# ProiectTSC_v38.net
KiCad netlist of a schematic drawn in EAGLE
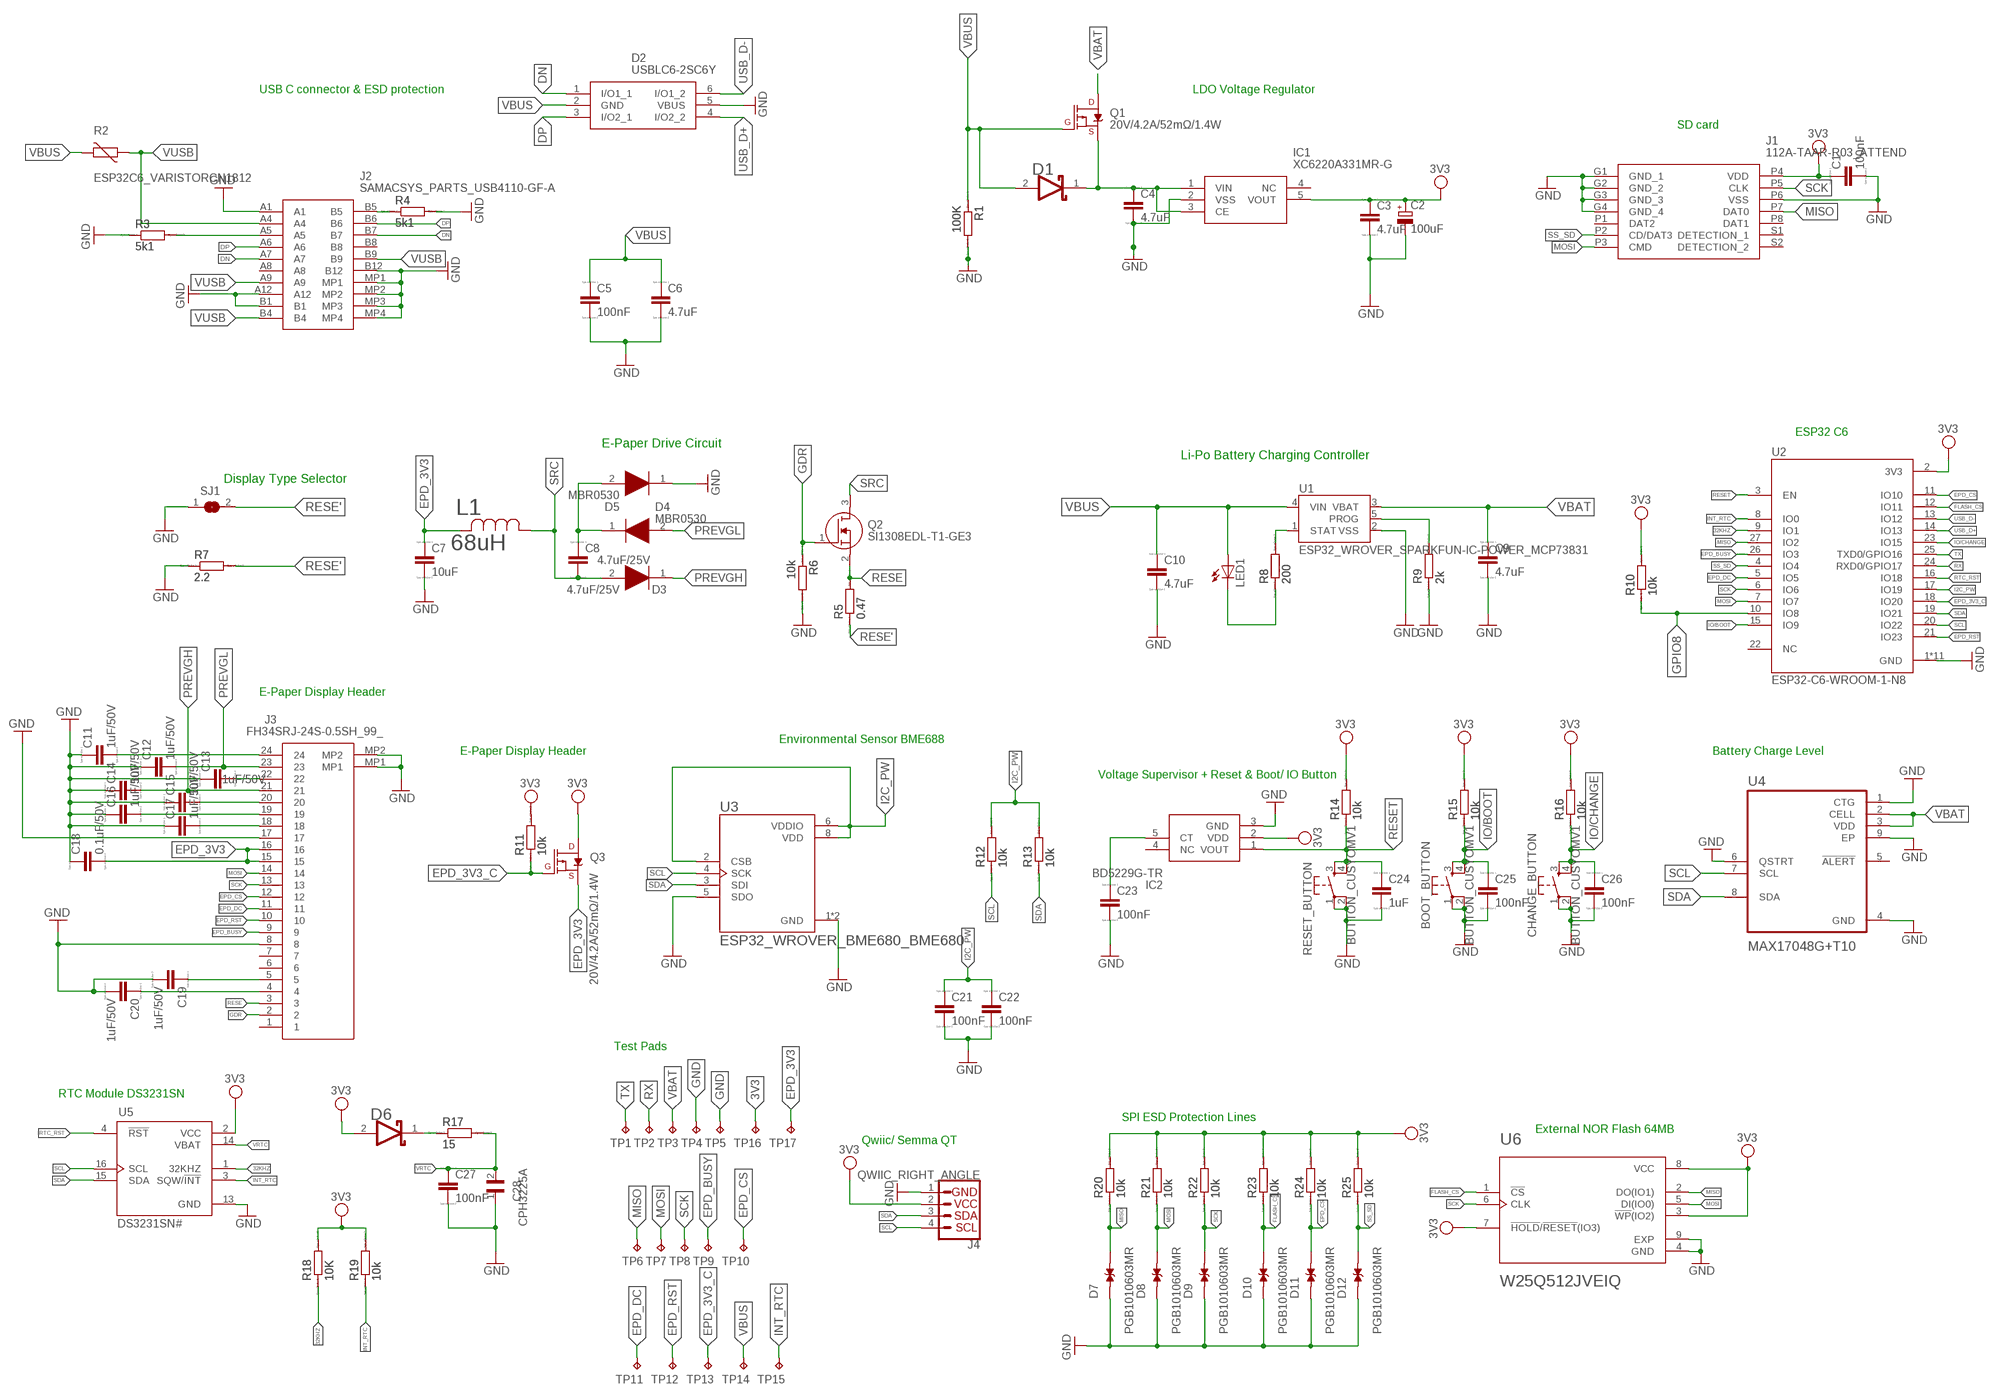
[diagram p0: schematic, sheet 1]

(export (version "E")
  (design (tool "Eeschema 10.0.6"))
  (components
    (comp (ref "BOOT_BUTTON")
      (value "BUTTON_CUSYOMV1")
      (footprint "eagle-import:MYBUTTON")
      (libsource (lib "eagle-import") (part "BUTTON_CUSYOMV1"))
    )
    (comp (ref "C1")
      (value "100nF")
      (footprint "eagle-import:EAGLE-LTSPICE_C0402")
      (libsource (lib "eagle-import") (part "EAGLE-LTSPICE_CC0402"))
    )
    (comp (ref "C2")
      (value "100uF")
      (footprint "eagle-import:RCL_CT3528")
      (libsource (lib "eagle-import") (part "RCL_CPOL-EUCT3528"))
    )
    (comp (ref "C3")
      (value "4.7uF")
      (footprint "eagle-import:ESP32_WROVER_EAGLE-LTSPICE_C0402")
      (libsource (lib "eagle-import") (part "ESP32_WROVER_EAGLE-LTSPICE_C"))
    )
    (comp (ref "C4")
      (value "4.7uF")
      (footprint "eagle-import:ESP32_WROVER_EAGLE-LTSPICE_C0402")
      (libsource (lib "eagle-import") (part "ESP32_WROVER_EAGLE-LTSPICE_C"))
    )
    (comp (ref "C5")
      (value "100nF")
      (footprint "eagle-import:EAGLE-LTSPICE_C0402")
      (libsource (lib "eagle-import") (part "EAGLE-LTSPICE_CC0402"))
    )
    (comp (ref "C6")
      (value "4.7uF")
      (footprint "eagle-import:EAGLE-LTSPICE_C0402")
      (libsource (lib "eagle-import") (part "EAGLE-LTSPICE_CC0402"))
    )
    (comp (ref "C7")
      (value "10uF")
      (footprint "eagle-import:EAGLE-LTSPICE_C0402")
      (libsource (lib "eagle-import") (part "EAGLE-LTSPICE_CC0402"))
    )
    (comp (ref "C8")
      (value "4.7uF/25V")
      (footprint "eagle-import:EAGLE-LTSPICE_C0402")
      (libsource (lib "eagle-import") (part "EAGLE-LTSPICE_CC0402"))
    )
    (comp (ref "C9")
      (value "4.7uF")
      (footprint "eagle-import:EAGLE-LTSPICE_C0402")
      (libsource (lib "eagle-import") (part "EAGLE-LTSPICE_CC0402"))
    )
    (comp (ref "C10")
      (value "4.7uF")
      (footprint "eagle-import:EAGLE-LTSPICE_C0402")
      (libsource (lib "eagle-import") (part "EAGLE-LTSPICE_CC0402"))
    )
    (comp (ref "C11")
      (value "1uF/50V")
      (footprint "eagle-import:EAGLE-LTSPICE_C0402")
      (libsource (lib "eagle-import") (part "EAGLE-LTSPICE_CC0402"))
    )
    (comp (ref "C12")
      (value "1uF/50V")
      (footprint "eagle-import:EAGLE-LTSPICE_C0402")
      (libsource (lib "eagle-import") (part "EAGLE-LTSPICE_CC0402"))
    )
    (comp (ref "C13")
      (value "1uF/50V")
      (footprint "eagle-import:EAGLE-LTSPICE_C0402")
      (libsource (lib "eagle-import") (part "EAGLE-LTSPICE_CC0402"))
    )
    (comp (ref "C14")
      (value "1uF/50V")
      (footprint "eagle-import:EAGLE-LTSPICE_C0402")
      (libsource (lib "eagle-import") (part "EAGLE-LTSPICE_CC0402"))
    )
    (comp (ref "C15")
      (value "1uF/50V")
      (footprint "eagle-import:EAGLE-LTSPICE_C0402")
      (libsource (lib "eagle-import") (part "EAGLE-LTSPICE_CC0402"))
    )
    (comp (ref "C16")
      (value "1uF/50V")
      (footprint "eagle-import:EAGLE-LTSPICE_C0402")
      (libsource (lib "eagle-import") (part "EAGLE-LTSPICE_CC0402"))
    )
    (comp (ref "C17")
      (value "1uF/50V")
      (footprint "eagle-import:EAGLE-LTSPICE_C0402")
      (libsource (lib "eagle-import") (part "EAGLE-LTSPICE_CC0402"))
    )
    (comp (ref "C18")
      (value "0.1uF/50V")
      (footprint "eagle-import:EAGLE-LTSPICE_C0402")
      (libsource (lib "eagle-import") (part "EAGLE-LTSPICE_CC0402"))
    )
    (comp (ref "C19")
      (value "1uF/50V")
      (footprint "eagle-import:EAGLE-LTSPICE_C0402")
      (libsource (lib "eagle-import") (part "EAGLE-LTSPICE_CC0402"))
    )
    (comp (ref "C20")
      (value "1uF/50V")
      (footprint "eagle-import:EAGLE-LTSPICE_C0402")
      (libsource (lib "eagle-import") (part "EAGLE-LTSPICE_CC0402"))
    )
    (comp (ref "C21")
      (value "100nF")
      (footprint "eagle-import:EAGLE-LTSPICE_C0402")
      (libsource (lib "eagle-import") (part "EAGLE-LTSPICE_CC0402"))
    )
    (comp (ref "C22")
      (value "100nF")
      (footprint "eagle-import:EAGLE-LTSPICE_C0402")
      (libsource (lib "eagle-import") (part "EAGLE-LTSPICE_CC0402"))
    )
    (comp (ref "C23")
      (value "100nF")
      (footprint "eagle-import:EAGLE-LTSPICE_C0402")
      (libsource (lib "eagle-import") (part "EAGLE-LTSPICE_CC0402"))
    )
    (comp (ref "C24")
      (value "1uF")
      (footprint "eagle-import:EAGLE-LTSPICE_C0402")
      (libsource (lib "eagle-import") (part "EAGLE-LTSPICE_CC0402"))
    )
    (comp (ref "C25")
      (value "100nF")
      (footprint "eagle-import:EAGLE-LTSPICE_C0402")
      (libsource (lib "eagle-import") (part "EAGLE-LTSPICE_CC0402"))
    )
    (comp (ref "C26")
      (value "100nF")
      (footprint "eagle-import:EAGLE-LTSPICE_C0402")
      (libsource (lib "eagle-import") (part "EAGLE-LTSPICE_CC0402"))
    )
    (comp (ref "C27")
      (value "100nF")
      (footprint "eagle-import:EAGLE-LTSPICE_C0402")
      (libsource (lib "eagle-import") (part "EAGLE-LTSPICE_CC0402"))
    )
    (comp (ref "C28")
      (value "CPH3225A")
      (footprint "eagle-import:CAPCP3225X100N")
      (fields (field (name "MF") "Seiko Instruments"))
      (libsource (lib "eagle-import") (part "CPH3225A"))
    )
    (comp (ref "CHANGE_BUTTON")
      (value "BUTTON_CUSYOMV1")
      (footprint "eagle-import:MYBUTTON")
      (libsource (lib "eagle-import") (part "BUTTON_CUSYOMV1"))
    )
    (comp (ref "D1")
      (value "ESP32_WROVER_AVX---SD0805S020S1R0_AVX_SD0805S020S1R0_0_0AVX_SD0805S020S1R0_0_0")
      (footprint "eagle-import:ESP32_WROVER_AVX---SD0805S020S1R0_AVX_SD0805S020S1R0_0")
      (fields
        (field (name "DIGIKEY_PART_NUMBER") "478-7800-1-ND")
        (field (name "MF") "AVX")
        (field (name "MOUSER_PART_NUMBER") "581-SD0805S020S1R0")
      )
      (libsource (lib "eagle-import") (part "ESP32_WROVER_AVX---SD0805S020S1R0_AVX_SD0805S020S1R0_0_0AVX_SD0805S020S1R0_0_0"))
    )
    (comp (ref "D2")
      (value "USBLC6-2SC6Y")
      (footprint "eagle-import:SOT95P280X145-6N")
      (fields (field (name "MF") "STMicroelectronics"))
      (libsource (lib "eagle-import") (part "USBLC6-2SC6Y"))
    )
    (comp (ref "D3")
      (value "4.7uF/25V")
      (footprint "eagle-import:SOD3716X135N")
      (fields (field (name "MF") "ON Semiconductor") (field (name "MP") "MBR0530"))
      (libsource (lib "eagle-import") (part "MBR0530"))
    )
    (comp (ref "D4")
      (value "MBR0530")
      (footprint "eagle-import:SOD3716X135N")
      (fields (field (name "MF") "ON Semiconductor"))
      (libsource (lib "eagle-import") (part "MBR0530"))
    )
    (comp (ref "D5")
      (value "MBR0530")
      (footprint "eagle-import:SOD3716X135N")
      (fields (field (name "MF") "ON Semiconductor"))
      (libsource (lib "eagle-import") (part "MBR0530"))
    )
    (comp (ref "D6")
      (value "ESP32_WROVER_AVX---SD0805S020S1R0_AVX_SD0805S020S1R0_0_0AVX_SD0805S020S1R0_0_0")
      (footprint "eagle-import:ESP32_WROVER_AVX---SD0805S020S1R0_AVX_SD0805S020S1R0_0")
      (fields
        (field (name "DIGIKEY_PART_NUMBER") "478-7800-1-ND")
        (field (name "MF") "AVX")
        (field (name "MOUSER_PART_NUMBER") "581-SD0805S020S1R0")
      )
      (libsource (lib "eagle-import") (part "ESP32_WROVER_AVX---SD0805S020S1R0_AVX_SD0805S020S1R0_0_0AVX_SD0805S020S1R0_0_0"))
    )
    (comp (ref "D7")
      (value "PGB1010603MR")
      (footprint "eagle-import:DIOC1608X36N")
      (fields (field (name "MF") "Littelfuse Inc."))
      (libsource (lib "eagle-import") (part "PGB1010603MR"))
    )
    (comp (ref "D8")
      (value "PGB1010603MR")
      (footprint "eagle-import:DIOC1608X36N")
      (fields (field (name "MF") "Littelfuse Inc."))
      (libsource (lib "eagle-import") (part "PGB1010603MR"))
    )
    (comp (ref "D9")
      (value "PGB1010603MR")
      (footprint "eagle-import:DIOC1608X36N")
      (fields (field (name "MF") "Littelfuse Inc."))
      (libsource (lib "eagle-import") (part "PGB1010603MR"))
    )
    (comp (ref "D10")
      (value "PGB1010603MR")
      (footprint "eagle-import:DIOC1608X36N")
      (fields (field (name "MF") "Littelfuse Inc."))
      (libsource (lib "eagle-import") (part "PGB1010603MR"))
    )
    (comp (ref "D11")
      (value "PGB1010603MR")
      (footprint "eagle-import:DIOC1608X36N")
      (fields (field (name "MF") "Littelfuse Inc."))
      (libsource (lib "eagle-import") (part "PGB1010603MR"))
    )
    (comp (ref "D12")
      (value "PGB1010603MR")
      (footprint "eagle-import:DIOC1608X36N")
      (fields (field (name "MF") "Littelfuse Inc."))
      (libsource (lib "eagle-import") (part "PGB1010603MR"))
    )
    (comp (ref "IC1")
      (value "XC6220A331MR-G")
      (footprint "eagle-import:SOT95P280X120-5N")
      (fields (field (name "MOUSER_PART_NUMBER") "865-XC6220A331MR-G"))
      (libsource (lib "eagle-import") (part "XC6220A331MR-G"))
    )
    (comp (ref "IC2")
      (value "BD5229G-TR")
      (footprint "eagle-import:SOT95P280X125-5N")
      (fields (field (name "MOUSER_PART_NUMBER") "755-BD5229G-TR"))
      (libsource (lib "eagle-import") (part "BD5229G-TR"))
    )
    (comp (ref "J1")
      (value "112A-TAAR-R03_ATTEND")
      (footprint "eagle-import:112ATAARR03ATTEND")
      (fields (field (name "MANUFACTURER_PART_NUMBER") "112A-TAAR-R03 ATTEND"))
      (libsource (lib "eagle-import") (part "112A-TAAR-R03_ATTEND"))
    )
    (comp (ref "J2")
      (value "SAMACSYS_PARTS_USB4110-GF-A")
      (footprint "eagle-import:SAMACSYS_PARTS_USB4110GFA")
      (fields
        (field (name "MANUFACTURER_PART_NUMBER") "USB4110-GF-A")
        (field (name "MOUSER_PART_NUMBER") "640-USB4110-GF-A")
      )
      (libsource (lib "eagle-import") (part "SAMACSYS_PARTS_USB4110-GF-A"))
    )
    (comp (ref "J3")
      (value "FH34SRJ-24S-0.5SH_99_")
      (footprint "eagle-import:FH34SRJ24S05SH99")
      (fields
        (field (name "MANUFACTURER_PART_NUMBER") "FH34SRJ-24S-0.5SH(99)")
        (field (name "MOUSER_PART_NUMBER") "798-FH34SRJ24S05SH99")
      )
      (libsource (lib "eagle-import") (part "FH34SRJ-24S-0.5SH_99_"))
    )
    (comp (ref "J4")
      (value "QWIIC_RIGHT_ANGLE")
      (footprint "eagle-import:JST04_1MM_RA")
      (libsource (lib "eagle-import") (part "QWIIC_CONNECTORJS-1MM"))
    )
    (comp (ref "L1")
      (value "68uH")
      (footprint "eagle-import:IND_4828-WE-TPC_WRE")
      (fields
        (field (name "MANUFACTURER_PART_NUMBER") "744043680")
        (field (name "COPYRIGHT") "Copyright (C) 2024 Ultra Librarian. All rights reserved.")
      )
      (libsource (lib "eagle-import") (part "744043680IND_4828-WE-TPC_WRE"))
    )
    (comp (ref "LED1")
      (value "ADAFRUIT_LEDCHIP-LED0603")
      (footprint "eagle-import:ADAFRUIT_CHIP-LED0603")
      (libsource (lib "eagle-import") (part "ADAFRUIT_LEDCHIP-LED0603"))
    )
    (comp (ref "Q1")
      (value "20V/4.2A/52mΩ/1.4W")
      (footprint "eagle-import:ESP32_WROVER_SPARKFUN-DISCRETESEMI_SOT23-3")
      (libsource (lib "eagle-import") (part "ESP32_WROVER_SPARKFUN-DISCRETESEMI_MOSFET_PCH-DMG2305UX-7"))
    )
    (comp (ref "Q2")
      (value "SI1308EDL-T1-GE3")
      (footprint "eagle-import:SOT65P210X110-3N")
      (fields (field (name "MF") "Vishay Siliconix"))
      (libsource (lib "eagle-import") (part "SI1308EDL-T1-GE3"))
    )
    (comp (ref "Q3")
      (value "20V/4.2A/52mΩ/1.4W")
      (footprint "eagle-import:ESP32_WROVER_SPARKFUN-DISCRETESEMI_SOT23-3")
      (libsource (lib "eagle-import") (part "ESP32_WROVER_SPARKFUN-DISCRETESEMI_MOSFET_PCH-DMG2305UX-7"))
    )
    (comp (ref "R1")
      (value "100K")
      (footprint "eagle-import:ESP32_WROVER_EAGLE-LTSPICE_R0402")
      (libsource (lib "eagle-import") (part "ESP32_WROVER_EAGLE-LTSPICE_RR0402"))
    )
    (comp (ref "R2")
      (value "ESP32C6_VARISTORCN1812")
      (footprint "eagle-import:ESP32C6_VARISTOR_CT_CN1812")
      (libsource (lib "eagle-import") (part "ESP32C6_VARISTORCN1812"))
    )
    (comp (ref "R3")
      (value "5k1")
      (footprint "eagle-import:ESP32_WROVER_EAGLE-LTSPICE_R0402")
      (libsource (lib "eagle-import") (part "ESP32_WROVER_EAGLE-LTSPICE_RR0402"))
    )
    (comp (ref "R4")
      (value "5k1")
      (footprint "eagle-import:ESP32_WROVER_EAGLE-LTSPICE_R0402")
      (libsource (lib "eagle-import") (part "ESP32_WROVER_EAGLE-LTSPICE_RR0402"))
    )
    (comp (ref "R5")
      (value "0.47")
      (footprint "eagle-import:ESP32_WROVER_EAGLE-LTSPICE_R0402")
      (libsource (lib "eagle-import") (part "ESP32_WROVER_EAGLE-LTSPICE_RR0402"))
    )
    (comp (ref "R6")
      (value "10k")
      (footprint "eagle-import:ESP32_WROVER_EAGLE-LTSPICE_R0402")
      (libsource (lib "eagle-import") (part "ESP32_WROVER_EAGLE-LTSPICE_RR0402"))
    )
    (comp (ref "R7")
      (value "2.2")
      (footprint "eagle-import:ESP32_WROVER_EAGLE-LTSPICE_R0402")
      (libsource (lib "eagle-import") (part "ESP32_WROVER_EAGLE-LTSPICE_RR0402"))
    )
    (comp (ref "R8")
      (value "200")
      (footprint "eagle-import:ESP32_WROVER_EAGLE-LTSPICE_R0402")
      (libsource (lib "eagle-import") (part "ESP32_WROVER_EAGLE-LTSPICE_RR0402"))
    )
    (comp (ref "R9")
      (value "2k")
      (footprint "eagle-import:ESP32_WROVER_EAGLE-LTSPICE_R0402")
      (libsource (lib "eagle-import") (part "ESP32_WROVER_EAGLE-LTSPICE_RR0402"))
    )
    (comp (ref "R10")
      (value "10k")
      (footprint "eagle-import:ESP32_WROVER_EAGLE-LTSPICE_R0402")
      (libsource (lib "eagle-import") (part "ESP32_WROVER_EAGLE-LTSPICE_RR0402"))
    )
    (comp (ref "R11")
      (value "10k")
      (footprint "eagle-import:ESP32_WROVER_EAGLE-LTSPICE_R0402")
      (libsource (lib "eagle-import") (part "ESP32_WROVER_EAGLE-LTSPICE_RR0402"))
    )
    (comp (ref "R12")
      (value "10k")
      (footprint "eagle-import:ESP32_WROVER_EAGLE-LTSPICE_R0402")
      (libsource (lib "eagle-import") (part "ESP32_WROVER_EAGLE-LTSPICE_RR0402"))
    )
    (comp (ref "R13")
      (value "10k")
      (footprint "eagle-import:ESP32_WROVER_EAGLE-LTSPICE_R0402")
      (libsource (lib "eagle-import") (part "ESP32_WROVER_EAGLE-LTSPICE_RR0402"))
    )
    (comp (ref "R14")
      (value "10k")
      (footprint "eagle-import:ESP32_WROVER_EAGLE-LTSPICE_R0402")
      (libsource (lib "eagle-import") (part "ESP32_WROVER_EAGLE-LTSPICE_RR0402"))
    )
    (comp (ref "R15")
      (value "10k")
      (footprint "eagle-import:ESP32_WROVER_EAGLE-LTSPICE_R0402")
      (libsource (lib "eagle-import") (part "ESP32_WROVER_EAGLE-LTSPICE_RR0402"))
    )
    (comp (ref "R16")
      (value "10k")
      (footprint "eagle-import:ESP32_WROVER_EAGLE-LTSPICE_R0402")
      (libsource (lib "eagle-import") (part "ESP32_WROVER_EAGLE-LTSPICE_RR0402"))
    )
    (comp (ref "R17")
      (value "15")
      (footprint "eagle-import:ESP32_WROVER_EAGLE-LTSPICE_R0402")
      (libsource (lib "eagle-import") (part "ESP32_WROVER_EAGLE-LTSPICE_RR0402"))
    )
    (comp (ref "R18")
      (value "10K")
      (footprint "eagle-import:ESP32_WROVER_EAGLE-LTSPICE_R0402")
      (libsource (lib "eagle-import") (part "ESP32_WROVER_EAGLE-LTSPICE_RR0402"))
    )
    (comp (ref "R19")
      (value "10k")
      (footprint "eagle-import:ESP32_WROVER_EAGLE-LTSPICE_R0402")
      (libsource (lib "eagle-import") (part "ESP32_WROVER_EAGLE-LTSPICE_RR0402"))
    )
    (comp (ref "R20")
      (value "10k")
      (footprint "eagle-import:ESP32_WROVER_EAGLE-LTSPICE_R0402")
      (libsource (lib "eagle-import") (part "ESP32_WROVER_EAGLE-LTSPICE_RR0402"))
    )
    (comp (ref "R21")
      (value "10k")
      (footprint "eagle-import:ESP32_WROVER_EAGLE-LTSPICE_R0402")
      (libsource (lib "eagle-import") (part "ESP32_WROVER_EAGLE-LTSPICE_RR0402"))
    )
    (comp (ref "R22")
      (value "10k")
      (footprint "eagle-import:ESP32_WROVER_EAGLE-LTSPICE_R0402")
      (libsource (lib "eagle-import") (part "ESP32_WROVER_EAGLE-LTSPICE_RR0402"))
    )
    (comp (ref "R23")
      (value "10k")
      (footprint "eagle-import:ESP32_WROVER_EAGLE-LTSPICE_R0402")
      (libsource (lib "eagle-import") (part "ESP32_WROVER_EAGLE-LTSPICE_RR0402"))
    )
    (comp (ref "R24")
      (value "10k")
      (footprint "eagle-import:ESP32_WROVER_EAGLE-LTSPICE_R0402")
      (libsource (lib "eagle-import") (part "ESP32_WROVER_EAGLE-LTSPICE_RR0402"))
    )
    (comp (ref "R25")
      (value "10k")
      (footprint "eagle-import:ESP32_WROVER_EAGLE-LTSPICE_R0402")
      (libsource (lib "eagle-import") (part "ESP32_WROVER_EAGLE-LTSPICE_RR0402"))
    )
    (comp (ref "RESET_BUTTON")
      (value "BUTTON_CUSYOMV1")
      (footprint "eagle-import:MYBUTTON")
      (libsource (lib "eagle-import") (part "BUTTON_CUSYOMV1"))
    )
    (comp (ref "SJ1") (value "SJ") (footprint "eagle-import:SJ") (libsource (lib "eagle-import") (part "SJ")))
    (comp (ref "TP1")
      (value "TPTP20R")
      (footprint "eagle-import:TP20R")
      (libsource (lib "eagle-import") (part "TPTP20R"))
    )
    (comp (ref "TP2")
      (value "TPTP20R")
      (footprint "eagle-import:TP20R")
      (libsource (lib "eagle-import") (part "TPTP20R"))
    )
    (comp (ref "TP3")
      (value "TPTP20R")
      (footprint "eagle-import:TP20R")
      (libsource (lib "eagle-import") (part "TPTP20R"))
    )
    (comp (ref "TP4")
      (value "TPTP20R")
      (footprint "eagle-import:TP20R")
      (libsource (lib "eagle-import") (part "TPTP20R"))
    )
    (comp (ref "TP5")
      (value "TPTP20R")
      (footprint "eagle-import:TP20R")
      (libsource (lib "eagle-import") (part "TPTP20R"))
    )
    (comp (ref "TP6")
      (value "TPTP20R")
      (footprint "eagle-import:TP20R")
      (libsource (lib "eagle-import") (part "TPTP20R"))
    )
    (comp (ref "TP7")
      (value "TPTP20R")
      (footprint "eagle-import:TP20R")
      (libsource (lib "eagle-import") (part "TPTP20R"))
    )
    (comp (ref "TP8")
      (value "TPTP20R")
      (footprint "eagle-import:TP20R")
      (libsource (lib "eagle-import") (part "TPTP20R"))
    )
    (comp (ref "TP9")
      (value "TPTP20R")
      (footprint "eagle-import:TP20R")
      (libsource (lib "eagle-import") (part "TPTP20R"))
    )
    (comp (ref "TP10")
      (value "TPTP20R")
      (footprint "eagle-import:TP20R")
      (libsource (lib "eagle-import") (part "TPTP20R"))
    )
    (comp (ref "TP11")
      (value "TPTP20R")
      (footprint "eagle-import:TP20R")
      (libsource (lib "eagle-import") (part "TPTP20R"))
    )
    (comp (ref "TP12")
      (value "TPTP20R")
      (footprint "eagle-import:TP20R")
      (libsource (lib "eagle-import") (part "TPTP20R"))
    )
    (comp (ref "TP13")
      (value "TPTP20R")
      (footprint "eagle-import:TP20R")
      (libsource (lib "eagle-import") (part "TPTP20R"))
    )
    (comp (ref "TP14")
      (value "TPTP20R")
      (footprint "eagle-import:TP20R")
      (libsource (lib "eagle-import") (part "TPTP20R"))
    )
    (comp (ref "TP15")
      (value "TPTP20R")
      (footprint "eagle-import:TP20R")
      (libsource (lib "eagle-import") (part "TPTP20R"))
    )
    (comp (ref "TP16")
      (value "TPTP20R")
      (footprint "eagle-import:TP20R")
      (libsource (lib "eagle-import") (part "TPTP20R"))
    )
    (comp (ref "TP17")
      (value "TPTP20R")
      (footprint "eagle-import:TP20R")
      (libsource (lib "eagle-import") (part "TPTP20R"))
    )
    (comp (ref "U1")
      (value "ESP32_WROVER_SPARKFUN-IC-POWER_MCP73831")
      (footprint "eagle-import:ESP32_WROVER_SPARKFUN-IC-POWER_SOT23-5")
      (libsource (lib "eagle-import") (part "ESP32_WROVER_SPARKFUN-IC-POWER_MCP73831"))
    )
    (comp (ref "U2")
      (value "ESP32-C6-WROOM-1-N8")
      (footprint "eagle-import:XCVR_ESP32-C6-WROOM-1-N8")
      (fields (field (name "MF") "Espressif Systems"))
      (libsource (lib "eagle-import") (part "ESP32-C6-WROOM-1-N8"))
    )
    (comp (ref "U3")
      (value "ESP32_WROVER_BME680_BME680")
      (footprint "eagle-import:ESP32_WROVER_BME680_PSON80P300X300X100-8N")
      (fields (field (name "MF") "Bosch Sensortec") (field (name "MP") "BME680"))
      (libsource (lib "eagle-import") (part "ESP32_WROVER_BME680_BME680"))
    )
    (comp (ref "U4")
      (value "MAX17048G+T10")
      (footprint "eagle-import:SON50P200X200X80-9N")
      (fields (field (name "MF") "Analog Devices"))
      (libsource (lib "eagle-import") (part "MAX17048G+T10"))
    )
    (comp (ref "U5")
      (value "DS3231SN#")
      (footprint "eagle-import:SOIC127P1032X265-16N")
      (fields (field (name "MF") "Analog Devices"))
      (libsource (lib "eagle-import") (part "DS3231SN#"))
    )
    (comp (ref "U6")
      (value "W25Q512JVEIQ")
      (footprint "eagle-import:SON127P600X800X80-9N")
      (fields (field (name "MF") "Winbond Electronics"))
      (libsource (lib "eagle-import") (part "W25Q512JVEIQ"))
    )
  )
  (nets
    (net (code "1") (name "3V3") (class "Default")
      (node (ref "C1") (pin "1") (pinfunction "1_1") (pintype "passive"))
      (node (ref "C2") (pin "+") (pinfunction "+_+") (pintype "passive"))
      (node (ref "C3") (pin "1") (pinfunction "1_1") (pintype "passive"))
      (node (ref "D6") (pin "2") (pinfunction "ANODE_2") (pintype "bidirectional"))
      (node (ref "IC1") (pin "5") (pinfunction "VOUT_5") (pintype "bidirectional"))
      (node (ref "IC2") (pin "2") (pinfunction "VDD_2") (pintype "bidirectional"))
      (node (ref "J1") (pin "P4") (pinfunction "VDD_P4") (pintype "bidirectional"))
      (node (ref "J4") (pin "2") (pinfunction "2_2") (pintype "power_in"))
      (node (ref "Q3") (pin "3") (pinfunction "D_3") (pintype "bidirectional"))
      (node (ref "R10") (pin "2") (pinfunction "2_2") (pintype "passive"))
      (node (ref "R11") (pin "2") (pinfunction "2_2") (pintype "passive"))
      (node (ref "R14") (pin "2") (pinfunction "2_2") (pintype "passive"))
      (node (ref "R15") (pin "2") (pinfunction "2_2") (pintype "passive"))
      (node (ref "R16") (pin "2") (pinfunction "2_2") (pintype "passive"))
      (node (ref "R18") (pin "2") (pinfunction "2_2") (pintype "passive"))
      (node (ref "R19") (pin "2") (pinfunction "2_2") (pintype "passive"))
      (node (ref "R20") (pin "2") (pinfunction "2_2") (pintype "passive"))
      (node (ref "R21") (pin "2") (pinfunction "2_2") (pintype "passive"))
      (node (ref "R22") (pin "2") (pinfunction "2_2") (pintype "passive"))
      (node (ref "R23") (pin "2") (pinfunction "2_2") (pintype "passive"))
      (node (ref "R24") (pin "2") (pinfunction "2_2") (pintype "passive"))
      (node (ref "R25") (pin "2") (pinfunction "2_2") (pintype "passive"))
      (node (ref "TP16") (pin "TP") (pinfunction "TP_TP") (pintype "input"))
      (node (ref "U2") (pin "2") (pinfunction "3V3_2") (pintype "power_in"))
      (node (ref "U5") (pin "2") (pinfunction "VCC_2") (pintype "power_in"))
      (node (ref "U6") (pin "3") (pinfunction "~{WP}(IO2)_3") (pintype "bidirectional"))
      (node (ref "U6") (pin "7") (pinfunction "~{HOLD}/~{RESET}(IO3)_7") (pintype "bidirectional"))
      (node (ref "U6") (pin "8") (pinfunction "VCC_8") (pintype "power_in"))
    )
    (net (code "2") (name "32KHZ") (class "Default")
      (node (ref "R18") (pin "1") (pinfunction "1_1") (pintype "passive"))
      (node (ref "U2") (pin "9") (pinfunction "IO1_9") (pintype "bidirectional"))
      (node (ref "U5") (pin "1") (pinfunction "32KHZ_1") (pintype "output"))
    )
    (net (code "3") (name "DN") (class "Default")
      (node (ref "D2") (pin "1") (pinfunction "I/O1_1_1") (pintype "bidirectional"))
      (node (ref "J2") (pin "A7") (pinfunction "A7_A7") (pintype "bidirectional"))
      (node (ref "J2") (pin "B7") (pinfunction "B7_B7") (pintype "bidirectional"))
    )
    (net (code "4") (name "DP") (class "Default")
      (node (ref "D2") (pin "3") (pinfunction "I/O2_1_3") (pintype "bidirectional"))
      (node (ref "J2") (pin "A6") (pinfunction "A6_A6") (pintype "bidirectional"))
      (node (ref "J2") (pin "B6") (pinfunction "B6_B6") (pintype "bidirectional"))
    )
    (net (code "5") (name "EPD_3V3") (class "Default")
      (node (ref "C18") (pin "2") (pinfunction "2_2") (pintype "passive"))
      (node (ref "C7") (pin "1") (pinfunction "1_1") (pintype "passive"))
      (node (ref "J3") (pin "15") (pinfunction "15_15") (pintype "bidirectional"))
      (node (ref "J3") (pin "16") (pinfunction "16_16") (pintype "bidirectional"))
      (node (ref "L1") (pin "2") (pinfunction "2_2") (pintype "passive"))
      (node (ref "Q3") (pin "2") (pinfunction "S_2") (pintype "bidirectional"))
      (node (ref "TP17") (pin "TP") (pinfunction "TP_TP") (pintype "input"))
    )
    (net (code "6") (name "EPD_3V3_C") (class "Default")
      (node (ref "Q3") (pin "1") (pinfunction "G_1") (pintype "bidirectional"))
      (node (ref "R11") (pin "1") (pinfunction "1_1") (pintype "passive"))
      (node (ref "TP13") (pin "TP") (pinfunction "TP_TP") (pintype "input"))
      (node (ref "U2") (pin "18") (pinfunction "IO20_18") (pintype "bidirectional"))
    )
    (net (code "7") (name "EPD_BUSY") (class "Default")
      (node (ref "J3") (pin "9") (pinfunction "9_9") (pintype "bidirectional"))
      (node (ref "TP9") (pin "TP") (pinfunction "TP_TP") (pintype "input"))
      (node (ref "U2") (pin "26") (pinfunction "IO3_26") (pintype "bidirectional"))
    )
    (net (code "8") (name "EPD_CS") (class "Default")
      (node (ref "D11") (pin "2") (pinfunction "2_2") (pintype "passive"))
      (node (ref "J3") (pin "12") (pinfunction "12_12") (pintype "bidirectional"))
      (node (ref "R24") (pin "1") (pinfunction "1_1") (pintype "passive"))
      (node (ref "TP10") (pin "TP") (pinfunction "TP_TP") (pintype "input"))
      (node (ref "U2") (pin "11") (pinfunction "IO10_11") (pintype "bidirectional"))
    )
    (net (code "9") (name "EPD_DC") (class "Default")
      (node (ref "J3") (pin "11") (pinfunction "11_11") (pintype "bidirectional"))
      (node (ref "TP11") (pin "TP") (pinfunction "TP_TP") (pintype "input"))
      (node (ref "U2") (pin "5") (pinfunction "IO5_5") (pintype "bidirectional"))
    )
    (net (code "10") (name "EPD_RST") (class "Default")
      (node (ref "J3") (pin "10") (pinfunction "10_10") (pintype "bidirectional"))
      (node (ref "TP12") (pin "TP") (pinfunction "TP_TP") (pintype "input"))
      (node (ref "U2") (pin "21") (pinfunction "IO23_21") (pintype "bidirectional"))
    )
    (net (code "11") (name "FLASH_CS") (class "Default")
      (node (ref "D10") (pin "2") (pinfunction "2_2") (pintype "passive"))
      (node (ref "R23") (pin "1") (pinfunction "1_1") (pintype "passive"))
      (node (ref "U2") (pin "12") (pinfunction "IO11_12") (pintype "bidirectional"))
      (node (ref "U6") (pin "1") (pinfunction "~{CS}_1") (pintype "input"))
    )
    (net (code "12") (name "GDR") (class "Default")
      (node (ref "J3") (pin "2") (pinfunction "2_2") (pintype "bidirectional"))
      (node (ref "Q2") (pin "1") (pinfunction "G_1") (pintype "bidirectional"))
      (node (ref "R6") (pin "1") (pinfunction "1_1") (pintype "passive"))
    )
    (net (code "13") (name "GND") (class "Default")
      (node (ref "BOOT_BUTTON") (pin "1") (pinfunction "1_1") (pintype "passive"))
      (node (ref "BOOT_BUTTON") (pin "2") (pinfunction "2_2") (pintype "passive"))
      (node (ref "C1") (pin "2") (pinfunction "2_2") (pintype "passive"))
      (node (ref "C10") (pin "2") (pinfunction "2_2") (pintype "passive"))
      (node (ref "C11") (pin "1") (pinfunction "1_1") (pintype "passive"))
      (node (ref "C12") (pin "1") (pinfunction "1_1") (pintype "passive"))
      (node (ref "C13") (pin "1") (pinfunction "1_1") (pintype "passive"))
      (node (ref "C14") (pin "1") (pinfunction "1_1") (pintype "passive"))
      (node (ref "C15") (pin "1") (pinfunction "1_1") (pintype "passive"))
      (node (ref "C16") (pin "1") (pinfunction "1_1") (pintype "passive"))
      (node (ref "C17") (pin "1") (pinfunction "1_1") (pintype "passive"))
      (node (ref "C18") (pin "1") (pinfunction "1_1") (pintype "passive"))
      (node (ref "C19") (pin "2") (pinfunction "2_2") (pintype "passive"))
      (node (ref "C2") (pin "-") (pinfunction "-_-") (pintype "passive"))
      (node (ref "C20") (pin "2") (pinfunction "2_2") (pintype "passive"))
      (node (ref "C21") (pin "2") (pinfunction "2_2") (pintype "passive"))
      (node (ref "C22") (pin "2") (pinfunction "2_2") (pintype "passive"))
      (node (ref "C23") (pin "2") (pinfunction "2_2") (pintype "passive"))
      (node (ref "C24") (pin "2") (pinfunction "2_2") (pintype "passive"))
      (node (ref "C25") (pin "2") (pinfunction "2_2") (pintype "passive"))
      (node (ref "C26") (pin "2") (pinfunction "2_2") (pintype "passive"))
      (node (ref "C27") (pin "2") (pinfunction "2_2") (pintype "passive"))
      (node (ref "C28") (pin "1") (pinfunction "1_1") (pintype "passive"))
      (node (ref "C3") (pin "2") (pinfunction "2_2") (pintype "passive"))
      (node (ref "C4") (pin "2") (pinfunction "2_2") (pintype "passive"))
      (node (ref "C5") (pin "2") (pinfunction "2_2") (pintype "passive"))
      (node (ref "C6") (pin "2") (pinfunction "2_2") (pintype "passive"))
      (node (ref "C7") (pin "2") (pinfunction "2_2") (pintype "passive"))
      (node (ref "C9") (pin "2") (pinfunction "2_2") (pintype "passive"))
      (node (ref "CHANGE_BUTTON") (pin "1") (pinfunction "1_1") (pintype "passive"))
      (node (ref "CHANGE_BUTTON") (pin "2") (pinfunction "2_2") (pintype "passive"))
      (node (ref "D10") (pin "1") (pinfunction "1_1") (pintype "passive"))
      (node (ref "D11") (pin "1") (pinfunction "1_1") (pintype "passive"))
      (node (ref "D12") (pin "1") (pinfunction "1_1") (pintype "passive"))
      (node (ref "D2") (pin "5") (pinfunction "VBUS_5") (pintype "bidirectional"))
      (node (ref "D5") (pin "1") (pinfunction "K_1") (pintype "bidirectional"))
      (node (ref "D7") (pin "1") (pinfunction "1_1") (pintype "passive"))
      (node (ref "D8") (pin "1") (pinfunction "1_1") (pintype "passive"))
      (node (ref "D9") (pin "1") (pinfunction "1_1") (pintype "passive"))
      (node (ref "IC1") (pin "2") (pinfunction "VSS_2") (pintype "bidirectional"))
      (node (ref "IC2") (pin "3") (pinfunction "GND_3") (pintype "bidirectional"))
      (node (ref "J1") (pin "G1") (pinfunction "GND_1_G1") (pintype "bidirectional"))
      (node (ref "J1") (pin "G2") (pinfunction "GND_2_G2") (pintype "bidirectional"))
      (node (ref "J1") (pin "G3") (pinfunction "GND_3_G3") (pintype "bidirectional"))
      (node (ref "J1") (pin "G4") (pinfunction "GND_4_G4") (pintype "bidirectional"))
      (node (ref "J1") (pin "P6") (pinfunction "VSS_P6") (pintype "bidirectional"))
      (node (ref "J2") (pin "A1") (pinfunction "A1_A1") (pintype "bidirectional"))
      (node (ref "J2") (pin "A12") (pinfunction "A12_A12") (pintype "bidirectional"))
      (node (ref "J2") (pin "B1") (pinfunction "B1_B1") (pintype "bidirectional"))
      (node (ref "J2") (pin "B12") (pinfunction "B12_B12") (pintype "bidirectional"))
      (node (ref "J2") (pin "MP1") (pinfunction "MP1_MP1") (pintype "bidirectional"))
      (node (ref "J2") (pin "MP2") (pinfunction "MP2_MP2") (pintype "bidirectional"))
      (node (ref "J2") (pin "MP3") (pinfunction "MP3_MP3") (pintype "bidirectional"))
      (node (ref "J2") (pin "MP4") (pinfunction "MP4_MP4") (pintype "bidirectional"))
      (node (ref "J3") (pin "17") (pinfunction "17_17") (pintype "bidirectional"))
      (node (ref "J3") (pin "8") (pinfunction "8_8") (pintype "bidirectional"))
      (node (ref "J3") (pin "MP1") (pinfunction "MP1_MP1") (pintype "bidirectional"))
      (node (ref "J3") (pin "MP2") (pinfunction "MP2_MP2") (pintype "bidirectional"))
      (node (ref "J4") (pin "1") (pinfunction "1_1") (pintype "power_in"))
      (node (ref "R1") (pin "2") (pinfunction "2_2") (pintype "passive"))
      (node (ref "R3") (pin "1") (pinfunction "1_1") (pintype "passive"))
      (node (ref "R4") (pin "2") (pinfunction "2_2") (pintype "passive"))
      (node (ref "R6") (pin "2") (pinfunction "2_2") (pintype "passive"))
      (node (ref "R7") (pin "1") (pinfunction "1_1") (pintype "passive"))
      (node (ref "R9") (pin "1") (pinfunction "1_1") (pintype "passive"))
      (node (ref "RESET_BUTTON") (pin "1") (pinfunction "1_1") (pintype "passive"))
      (node (ref "RESET_BUTTON") (pin "2") (pinfunction "2_2") (pintype "passive"))
      (node (ref "SJ1") (pin "1") (pinfunction "1_1") (pintype "passive"))
      (node (ref "TP4") (pin "TP") (pinfunction "TP_TP") (pintype "input"))
      (node (ref "TP5") (pin "TP") (pinfunction "TP_TP") (pintype "input"))
      (node (ref "U1") (pin "2") (pinfunction "VSS_2") (pintype "power_in"))
      (node (ref "U2") (pin "1") (pinfunction "GND_1") (pintype "power_in"))
      (node (ref "U2") (pin "28") (pinfunction "GND_28") (pintype "power_in"))
      (node (ref "U2") (pin "29_1") (pinfunction "GND_29_1") (pintype "power_in"))
      (node (ref "U2") (pin "29_2") (pinfunction "GND_29_2") (pintype "power_in"))
      (node (ref "U2") (pin "29_3") (pinfunction "GND_29_3") (pintype "power_in"))
      (node (ref "U2") (pin "29_4") (pinfunction "GND_29_4") (pintype "power_in"))
      (node (ref "U2") (pin "29_5") (pinfunction "GND_29_5") (pintype "power_in"))
      (node (ref "U2") (pin "29_6") (pinfunction "GND_29_6") (pintype "power_in"))
      (node (ref "U2") (pin "29_7") (pinfunction "GND_29_7") (pintype "power_in"))
      (node (ref "U2") (pin "29_8") (pinfunction "GND_29_8") (pintype "power_in"))
      (node (ref "U2") (pin "29_9") (pinfunction "GND_29_9") (pintype "power_in"))
      (node (ref "U3") (pin "1") (pinfunction "GND_1") (pintype "power_in"))
      (node (ref "U3") (pin "5") (pinfunction "SDO_5") (pintype "bidirectional"))
      (node (ref "U3") (pin "7") (pinfunction "GND_7") (pintype "power_in"))
      (node (ref "U4") (pin "1") (pinfunction "CTG_1") (pintype "power_in"))
      (node (ref "U4") (pin "4") (pinfunction "GND_4") (pintype "power_in"))
      (node (ref "U4") (pin "6") (pinfunction "QSTRT_6") (pintype "input"))
      (node (ref "U4") (pin "9") (pinfunction "EP_9") (pintype "power_in"))
      (node (ref "U5") (pin "13") (pinfunction "GND_13") (pintype "power_in"))
      (node (ref "U6") (pin "4") (pinfunction "GND_4") (pintype "power_in"))
      (node (ref "U6") (pin "9") (pinfunction "EXP_9") (pintype "passive"))
    )
    (net (code "14") (name "GPIO8") (class "Default")
      (node (ref "R10") (pin "1") (pinfunction "1_1") (pintype "passive"))
      (node (ref "U2") (pin "10") (pinfunction "IO8_10") (pintype "bidirectional"))
    )
    (net (code "15") (name "I2C_PW") (class "Default")
      (node (ref "C21") (pin "1") (pinfunction "1_1") (pintype "passive"))
      (node (ref "C22") (pin "1") (pinfunction "1_1") (pintype "passive"))
      (node (ref "R12") (pin "2") (pinfunction "2_2") (pintype "passive"))
      (node (ref "R13") (pin "2") (pinfunction "2_2") (pintype "passive"))
      (node (ref "U2") (pin "17") (pinfunction "IO19_17") (pintype "bidirectional"))
      (node (ref "U3") (pin "2") (pinfunction "CSB_2") (pintype "input"))
      (node (ref "U3") (pin "6") (pinfunction "VDDIO_6") (pintype "power_in"))
      (node (ref "U3") (pin "8") (pinfunction "VDD_8") (pintype "power_in"))
    )
    (net (code "16") (name "INT_RTC") (class "Default")
      (node (ref "R19") (pin "1") (pinfunction "1_1") (pintype "passive"))
      (node (ref "TP15") (pin "TP") (pinfunction "TP_TP") (pintype "input"))
      (node (ref "U2") (pin "8") (pinfunction "IO0_8") (pintype "bidirectional"))
      (node (ref "U5") (pin "3") (pinfunction "SQW/~{INT}_3") (pintype "output"))
    )
    (net (code "17") (name "IO{slash}BOOT") (class "Default")
      (node (ref "BOOT_BUTTON") (pin "3") (pinfunction "3_3") (pintype "passive"))
      (node (ref "BOOT_BUTTON") (pin "4") (pinfunction "4_4") (pintype "passive"))
      (node (ref "C25") (pin "1") (pinfunction "1_1") (pintype "passive"))
      (node (ref "R15") (pin "1") (pinfunction "1_1") (pintype "passive"))
      (node (ref "U2") (pin "15") (pinfunction "IO9_15") (pintype "bidirectional"))
    )
    (net (code "18") (name "IO{slash}CHANGE") (class "Default")
      (node (ref "C26") (pin "1") (pinfunction "1_1") (pintype "passive"))
      (node (ref "CHANGE_BUTTON") (pin "3") (pinfunction "3_3") (pintype "passive"))
      (node (ref "CHANGE_BUTTON") (pin "4") (pinfunction "4_4") (pintype "passive"))
      (node (ref "R16") (pin "1") (pinfunction "1_1") (pintype "passive"))
      (node (ref "U2") (pin "23") (pinfunction "IO15_23") (pintype "bidirectional"))
    )
    (net (code "19") (name "MISO") (class "Default")
      (node (ref "D7") (pin "2") (pinfunction "2_2") (pintype "passive"))
      (node (ref "J1") (pin "P7") (pinfunction "DAT0_P7") (pintype "bidirectional"))
      (node (ref "R20") (pin "1") (pinfunction "1_1") (pintype "passive"))
      (node (ref "TP6") (pin "TP") (pinfunction "TP_TP") (pintype "input"))
      (node (ref "U2") (pin "27") (pinfunction "IO2_27") (pintype "bidirectional"))
      (node (ref "U6") (pin "2") (pinfunction "DO(IO1)_2") (pintype "bidirectional"))
    )
    (net (code "20") (name "MOSI") (class "Default")
      (node (ref "D8") (pin "2") (pinfunction "2_2") (pintype "passive"))
      (node (ref "J1") (pin "P3") (pinfunction "CMD_P3") (pintype "bidirectional"))
      (node (ref "J3") (pin "14") (pinfunction "14_14") (pintype "bidirectional"))
      (node (ref "R21") (pin "1") (pinfunction "1_1") (pintype "passive"))
      (node (ref "TP7") (pin "TP") (pinfunction "TP_TP") (pintype "input"))
      (node (ref "U2") (pin "7") (pinfunction "IO7_7") (pintype "bidirectional"))
      (node (ref "U6") (pin "5") (pinfunction "DI(IO0)_5") (pintype "bidirectional"))
    )
    (net (code "21") (name "Net-(C11-Pad2)") (class "Default")
      (node (ref "C11") (pin "2") (pinfunction "2_2") (pintype "passive"))
      (node (ref "J3") (pin "24") (pinfunction "24_24") (pintype "bidirectional"))
    )
    (net (code "22") (name "Net-(C13-Pad2)") (class "Default")
      (node (ref "C13") (pin "2") (pinfunction "2_2") (pintype "passive"))
      (node (ref "J3") (pin "22") (pinfunction "22_22") (pintype "bidirectional"))
    )
    (net (code "23") (name "Net-(C15-Pad2)") (class "Default")
      (node (ref "C15") (pin "2") (pinfunction "2_2") (pintype "passive"))
      (node (ref "J3") (pin "20") (pinfunction "20_20") (pintype "bidirectional"))
    )
    (net (code "24") (name "Net-(C16-Pad2)") (class "Default")
      (node (ref "C16") (pin "2") (pinfunction "2_2") (pintype "passive"))
      (node (ref "J3") (pin "19") (pinfunction "19_19") (pintype "bidirectional"))
    )
    (net (code "25") (name "Net-(C17-Pad2)") (class "Default")
      (node (ref "C17") (pin "2") (pinfunction "2_2") (pintype "passive"))
      (node (ref "J3") (pin "18") (pinfunction "18_18") (pintype "bidirectional"))
    )
    (net (code "26") (name "Net-(C19-Pad1)") (class "Default")
      (node (ref "C19") (pin "1") (pinfunction "1_1") (pintype "passive"))
      (node (ref "J3") (pin "5") (pinfunction "5_5") (pintype "bidirectional"))
    )
    (net (code "27") (name "Net-(C20-Pad1)") (class "Default")
      (node (ref "C20") (pin "1") (pinfunction "1_1") (pintype "passive"))
      (node (ref "J3") (pin "4") (pinfunction "4_4") (pintype "bidirectional"))
    )
    (net (code "28") (name "Net-(D1-CATHODE)") (class "Default")
      (node (ref "C4") (pin "1") (pinfunction "1_1") (pintype "passive"))
      (node (ref "D1") (pin "1") (pinfunction "CATHODE_1") (pintype "bidirectional"))
      (node (ref "IC1") (pin "1") (pinfunction "VIN_1") (pintype "bidirectional"))
      (node (ref "IC1") (pin "3") (pinfunction "CE_3") (pintype "bidirectional"))
      (node (ref "Q1") (pin "2") (pinfunction "S_2") (pintype "bidirectional"))
    )
    (net (code "29") (name "Net-(D4-K)") (class "Default")
      (node (ref "C8") (pin "1") (pinfunction "1_1") (pintype "passive"))
      (node (ref "D4") (pin "1") (pinfunction "K_1") (pintype "bidirectional"))
      (node (ref "D5") (pin "2") (pinfunction "A_2") (pintype "bidirectional"))
    )
    (net (code "30") (name "Net-(D6-CATHODE)") (class "Default")
      (node (ref "D6") (pin "1") (pinfunction "CATHODE_1") (pintype "bidirectional"))
      (node (ref "R17") (pin "1") (pinfunction "1_1") (pintype "passive"))
    )
    (net (code "31") (name "Net-(IC2-CT)") (class "Default")
      (node (ref "C23") (pin "1") (pinfunction "1_1") (pintype "passive"))
      (node (ref "IC2") (pin "5") (pinfunction "CT_5") (pintype "bidirectional"))
    )
    (net (code "32") (name "Net-(J2-PadA5)") (class "Default")
      (node (ref "J2") (pin "A5") (pinfunction "A5_A5") (pintype "bidirectional"))
      (node (ref "R3") (pin "2") (pinfunction "2_2") (pintype "passive"))
    )
    (net (code "33") (name "Net-(J2-PadB5)") (class "Default")
      (node (ref "J2") (pin "B5") (pinfunction "B5_B5") (pintype "bidirectional"))
      (node (ref "R4") (pin "1") (pinfunction "1_1") (pintype "passive"))
    )
    (net (code "34") (name "Net-(LED1-PadC)") (class "Default")
      (node (ref "LED1") (pin "C") (pinfunction "C_C") (pintype "passive"))
      (node (ref "R8") (pin "1") (pinfunction "1_1") (pintype "passive"))
    )
    (net (code "35") (name "Net-(U1-PROG)") (class "Default")
      (node (ref "R9") (pin "2") (pinfunction "2_2") (pintype "passive"))
      (node (ref "U1") (pin "5") (pinfunction "PROG_5") (pintype "input"))
    )
    (net (code "36") (name "Net-(U1-STAT)") (class "Default")
      (node (ref "R8") (pin "2") (pinfunction "2_2") (pintype "passive"))
      (node (ref "U1") (pin "1") (pinfunction "STAT_1") (pintype "output"))
    )
    (net (code "37") (name "PREVGH") (class "Default")
      (node (ref "C14") (pin "2") (pinfunction "2_2") (pintype "passive"))
      (node (ref "D3") (pin "1") (pinfunction "K_1") (pintype "bidirectional"))
      (node (ref "J3") (pin "21") (pinfunction "21_21") (pintype "bidirectional"))
    )
    (net (code "38") (name "PREVGL") (class "Default")
      (node (ref "C12") (pin "2") (pinfunction "2_2") (pintype "passive"))
      (node (ref "D4") (pin "2") (pinfunction "A_2") (pintype "bidirectional"))
      (node (ref "J3") (pin "23") (pinfunction "23_23") (pintype "bidirectional"))
    )
    (net (code "39") (name "RESE") (class "Default")
      (node (ref "J3") (pin "3") (pinfunction "3_3") (pintype "bidirectional"))
      (node (ref "Q2") (pin "2") (pinfunction "S_2") (pintype "bidirectional"))
      (node (ref "R5") (pin "2") (pinfunction "2_2") (pintype "passive"))
    )
    (net (code "40") (name "RESE'") (class "Default")
      (node (ref "R5") (pin "1") (pinfunction "1_1") (pintype "passive"))
      (node (ref "R7") (pin "2") (pinfunction "2_2") (pintype "passive"))
      (node (ref "SJ1") (pin "2") (pinfunction "2_2") (pintype "passive"))
    )
    (net (code "41") (name "RESET") (class "Default")
      (node (ref "C24") (pin "1") (pinfunction "1_1") (pintype "passive"))
      (node (ref "IC2") (pin "1") (pinfunction "VOUT_1") (pintype "bidirectional"))
      (node (ref "R14") (pin "1") (pinfunction "1_1") (pintype "passive"))
      (node (ref "RESET_BUTTON") (pin "3") (pinfunction "3_3") (pintype "passive"))
      (node (ref "RESET_BUTTON") (pin "4") (pinfunction "4_4") (pintype "passive"))
      (node (ref "U2") (pin "3") (pinfunction "EN_3") (pintype "input"))
    )
    (net (code "42") (name "RTC_RST") (class "Default")
      (node (ref "U2") (pin "16") (pinfunction "IO18_16") (pintype "bidirectional"))
      (node (ref "U5") (pin "4") (pinfunction "~{RST}_4") (pintype "input"))
    )
    (net (code "43") (name "RX") (class "Default")
      (node (ref "TP2") (pin "TP") (pinfunction "TP_TP") (pintype "input"))
      (node (ref "U2") (pin "24") (pinfunction "RXD0/GPIO17_24") (pintype "bidirectional"))
    )
    (net (code "44") (name "SCK") (class "Default")
      (node (ref "D9") (pin "2") (pinfunction "2_2") (pintype "passive"))
      (node (ref "J1") (pin "P5") (pinfunction "CLK_P5") (pintype "bidirectional"))
      (node (ref "J3") (pin "13") (pinfunction "13_13") (pintype "bidirectional"))
      (node (ref "R22") (pin "1") (pinfunction "1_1") (pintype "passive"))
      (node (ref "TP8") (pin "TP") (pinfunction "TP_TP") (pintype "input"))
      (node (ref "U2") (pin "6") (pinfunction "IO6_6") (pintype "bidirectional"))
      (node (ref "U6") (pin "6") (pinfunction "CLK_6") (pintype "input"))
    )
    (net (code "45") (name "SCL") (class "Default")
      (node (ref "J4") (pin "4") (pinfunction "4_4") (pintype "passive"))
      (node (ref "R12") (pin "1") (pinfunction "1_1") (pintype "passive"))
      (node (ref "U2") (pin "20") (pinfunction "IO22_20") (pintype "bidirectional"))
      (node (ref "U3") (pin "4") (pinfunction "SCK_4") (pintype "input"))
      (node (ref "U4") (pin "7") (pinfunction "SCL_7") (pintype "input"))
      (node (ref "U5") (pin "16") (pinfunction "SCL_16") (pintype "input"))
    )
    (net (code "46") (name "SDA") (class "Default")
      (node (ref "J4") (pin "3") (pinfunction "3_3") (pintype "passive"))
      (node (ref "R13") (pin "1") (pinfunction "1_1") (pintype "passive"))
      (node (ref "U2") (pin "19") (pinfunction "IO21_19") (pintype "bidirectional"))
      (node (ref "U3") (pin "3") (pinfunction "SDI_3") (pintype "bidirectional"))
      (node (ref "U4") (pin "8") (pinfunction "SDA_8") (pintype "bidirectional"))
      (node (ref "U5") (pin "15") (pinfunction "SDA_15") (pintype "bidirectional"))
    )
    (net (code "47") (name "SRC") (class "Default")
      (node (ref "C8") (pin "2") (pinfunction "2_2") (pintype "passive"))
      (node (ref "D3") (pin "2") (pinfunction "A_2") (pintype "bidirectional"))
      (node (ref "L1") (pin "1") (pinfunction "1_1") (pintype "passive"))
      (node (ref "Q2") (pin "3") (pinfunction "D_3") (pintype "bidirectional"))
    )
    (net (code "48") (name "SS_SD") (class "Default")
      (node (ref "D12") (pin "2") (pinfunction "2_2") (pintype "passive"))
      (node (ref "J1") (pin "P2") (pinfunction "CD/DAT3_P2") (pintype "bidirectional"))
      (node (ref "R25") (pin "1") (pinfunction "1_1") (pintype "passive"))
      (node (ref "U2") (pin "4") (pinfunction "IO4_4") (pintype "bidirectional"))
    )
    (net (code "49") (name "TX") (class "Default")
      (node (ref "TP1") (pin "TP") (pinfunction "TP_TP") (pintype "input"))
      (node (ref "U2") (pin "25") (pinfunction "TXD0/GPIO16_25") (pintype "bidirectional"))
    )
    (net (code "50") (name "USB_D+") (class "Default")
      (node (ref "D2") (pin "4") (pinfunction "I/O2_2_4") (pintype "bidirectional"))
      (node (ref "U2") (pin "14") (pinfunction "IO13_14") (pintype "bidirectional"))
    )
    (net (code "51") (name "USB_D-") (class "Default")
      (node (ref "D2") (pin "6") (pinfunction "I/O1_2_6") (pintype "bidirectional"))
      (node (ref "U2") (pin "13") (pinfunction "IO12_13") (pintype "bidirectional"))
    )
    (net (code "52") (name "VBAT") (class "Default")
      (node (ref "C9") (pin "1") (pinfunction "1_1") (pintype "passive"))
      (node (ref "Q1") (pin "3") (pinfunction "D_3") (pintype "bidirectional"))
      (node (ref "TP3") (pin "TP") (pinfunction "TP_TP") (pintype "input"))
      (node (ref "U1") (pin "3") (pinfunction "VBAT_3") (pintype "power_in"))
      (node (ref "U4") (pin "2") (pinfunction "CELL_2") (pintype "power_in"))
      (node (ref "U4") (pin "3") (pinfunction "VDD_3") (pintype "power_in"))
    )
    (net (code "53") (name "VBUS") (class "Default")
      (node (ref "C10") (pin "1") (pinfunction "1_1") (pintype "passive"))
      (node (ref "C5") (pin "1") (pinfunction "1_1") (pintype "passive"))
      (node (ref "C6") (pin "1") (pinfunction "1_1") (pintype "passive"))
      (node (ref "D1") (pin "2") (pinfunction "ANODE_2") (pintype "bidirectional"))
      (node (ref "D2") (pin "2") (pinfunction "GND_2") (pintype "bidirectional"))
      (node (ref "LED1") (pin "A") (pinfunction "A_A") (pintype "passive"))
      (node (ref "Q1") (pin "1") (pinfunction "G_1") (pintype "bidirectional"))
      (node (ref "R1") (pin "1") (pinfunction "1_1") (pintype "passive"))
      (node (ref "R2") (pin "2") (pinfunction "2_2") (pintype "passive"))
      (node (ref "TP14") (pin "TP") (pinfunction "TP_TP") (pintype "input"))
      (node (ref "U1") (pin "4") (pinfunction "VIN_4") (pintype "power_in"))
    )
    (net (code "54") (name "VRTC") (class "Default")
      (node (ref "C27") (pin "1") (pinfunction "1_1") (pintype "passive"))
      (node (ref "C28") (pin "2") (pinfunction "2_2") (pintype "passive"))
      (node (ref "R17") (pin "2") (pinfunction "2_2") (pintype "passive"))
      (node (ref "U5") (pin "14") (pinfunction "VBAT_14") (pintype "power_in"))
    )
    (net (code "55") (name "VUSB") (class "Default")
      (node (ref "J2") (pin "A4") (pinfunction "A4_A4") (pintype "bidirectional"))
      (node (ref "J2") (pin "A9") (pinfunction "A9_A9") (pintype "bidirectional"))
      (node (ref "J2") (pin "B4") (pinfunction "B4_B4") (pintype "bidirectional"))
      (node (ref "J2") (pin "B9") (pinfunction "B9_B9") (pintype "bidirectional"))
      (node (ref "R2") (pin "1") (pinfunction "1_1") (pintype "passive"))
    )
    (net (code "56") (name "unconnected-(IC1-NC-Pad4)") (class "Default")
      (node (ref "IC1") (pin "4") (pinfunction "NC_4") (pintype "no_connect"))
    )
    (net (code "57") (name "unconnected-(IC2-NC-Pad4)") (class "Default")
      (node (ref "IC2") (pin "4") (pinfunction "NC_4") (pintype "no_connect"))
    )
    (net (code "58") (name "unconnected-(J1-DAT1-PadP8)") (class "Default")
      (node (ref "J1") (pin "P8") (pinfunction "DAT1_P8") (pintype "bidirectional"))
    )
    (net (code "59") (name "unconnected-(J1-DAT2-PadP1)") (class "Default")
      (node (ref "J1") (pin "P1") (pinfunction "DAT2_P1") (pintype "bidirectional"))
    )
    (net (code "60") (name "unconnected-(J1-DETECTION_1-PadS1)") (class "Default")
      (node (ref "J1") (pin "S1") (pinfunction "DETECTION_1_S1") (pintype "bidirectional"))
    )
    (net (code "61") (name "unconnected-(J1-DETECTION_2-PadS2)") (class "Default")
      (node (ref "J1") (pin "S2") (pinfunction "DETECTION_2_S2") (pintype "bidirectional"))
    )
    (net (code "62") (name "unconnected-(J2-PadA8)") (class "Default")
      (node (ref "J2") (pin "A8") (pinfunction "A8_A8") (pintype "bidirectional"))
    )
    (net (code "63") (name "unconnected-(J2-PadB8)") (class "Default")
      (node (ref "J2") (pin "B8") (pinfunction "B8_B8") (pintype "bidirectional"))
    )
    (net (code "64") (name "unconnected-(J3-Pad1)") (class "Default")
      (node (ref "J3") (pin "1") (pinfunction "1_1") (pintype "bidirectional"))
    )
    (net (code "65") (name "unconnected-(J3-Pad6)") (class "Default")
      (node (ref "J3") (pin "6") (pinfunction "6_6") (pintype "bidirectional"))
    )
    (net (code "66") (name "unconnected-(J3-Pad7)") (class "Default")
      (node (ref "J3") (pin "7") (pinfunction "7_7") (pintype "bidirectional"))
    )
    (net (code "67") (name "unconnected-(U2-NC-Pad22)") (class "Default")
      (node (ref "U2") (pin "22") (pinfunction "NC_22") (pintype "no_connect"))
    )
    (net (code "68") (name "unconnected-(U4-~{ALERT}-Pad5)") (class "Default")
      (node (ref "U4") (pin "5") (pinfunction "~{ALERT}_5") (pintype "output"))
    )
  )
)
